# kulgurpowerproto.net
KiCad netlist of a schematic drawn in EAGLE
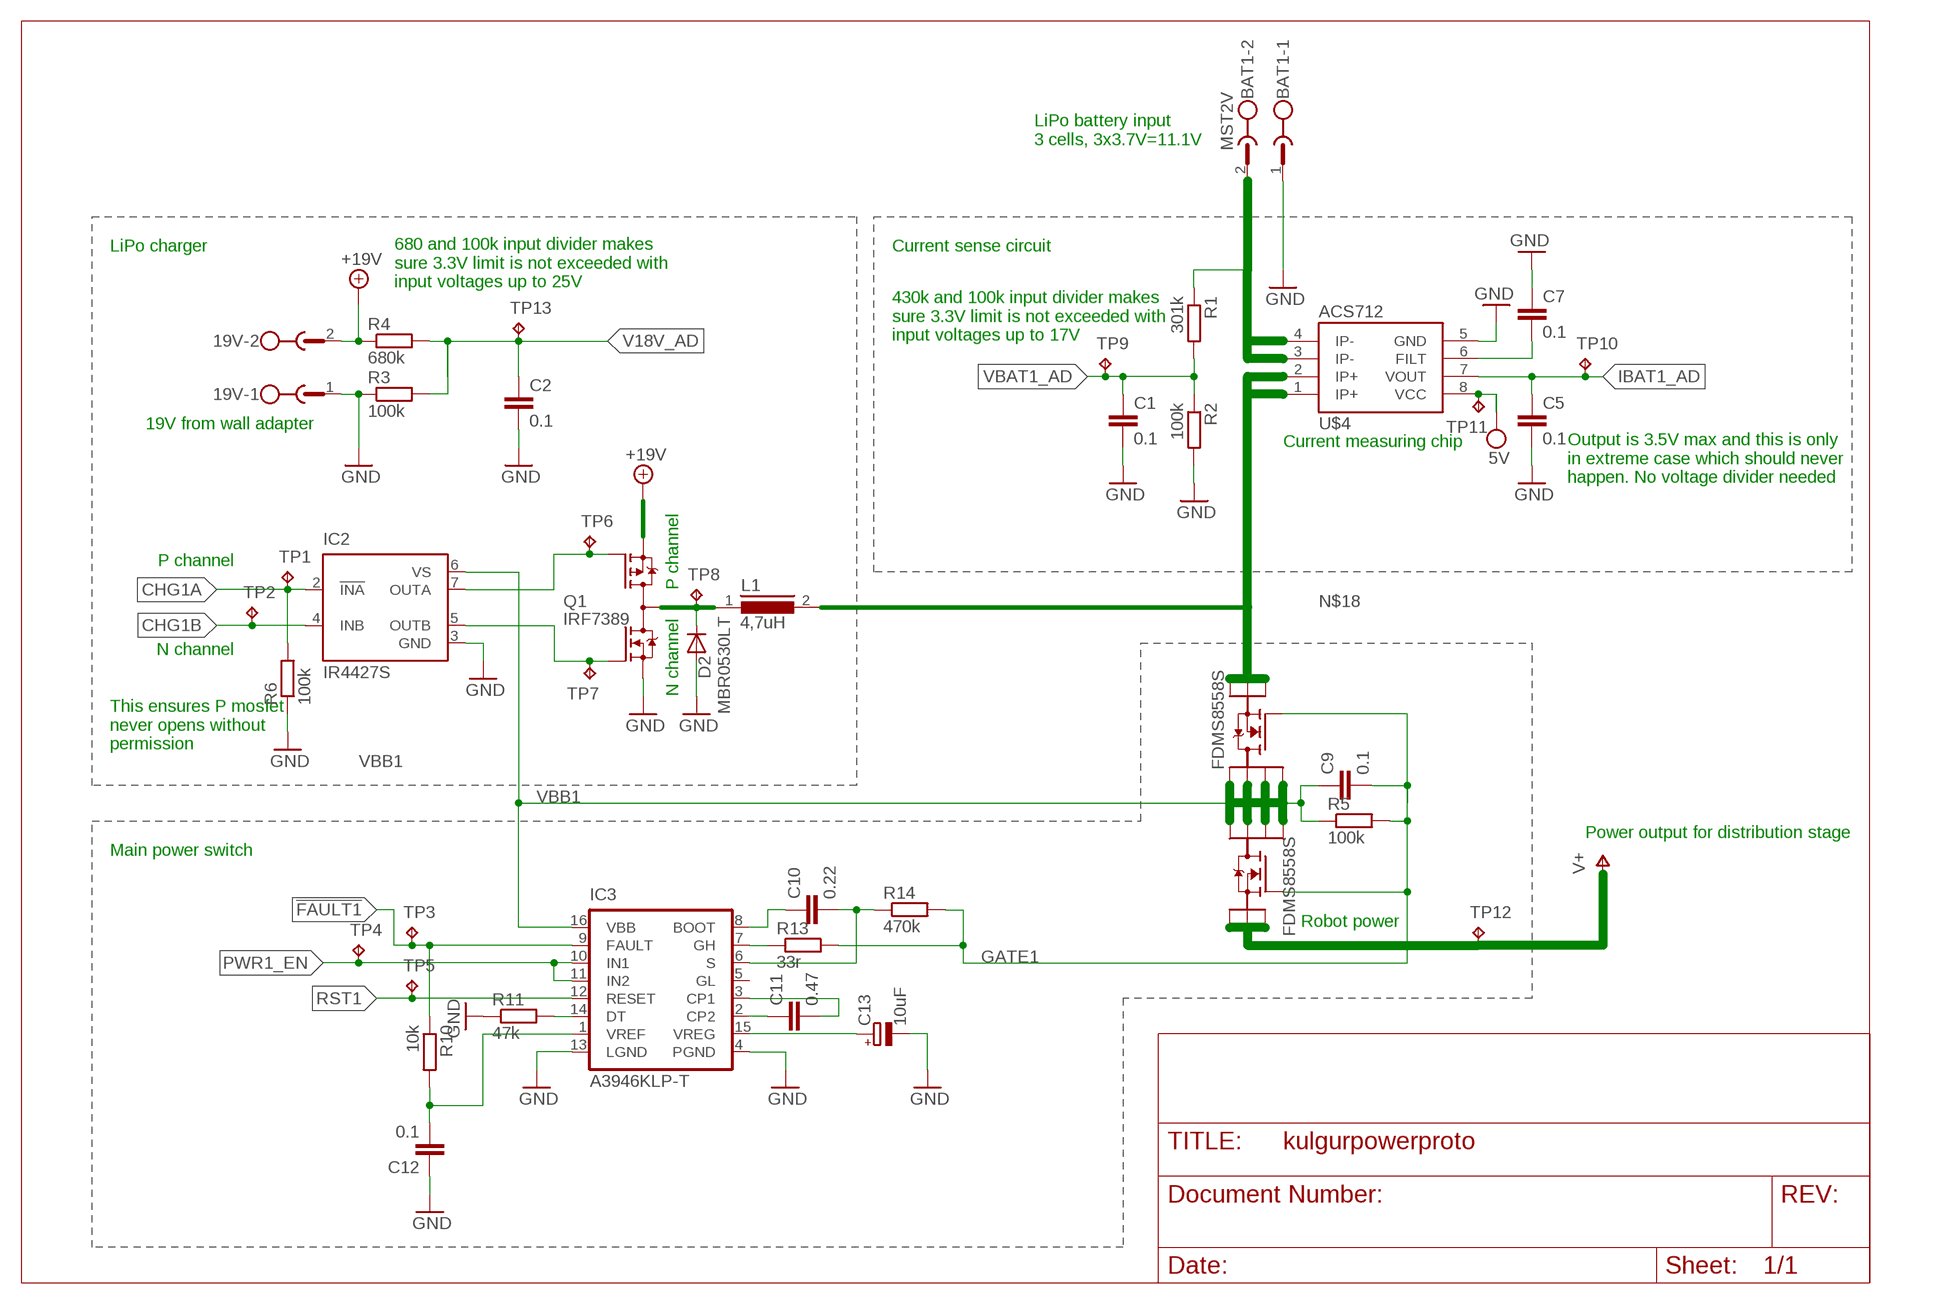
[diagram p0: schematic, sheet 1]

(export (version "E")
  (design (tool "Eeschema 10.0.6"))
  (components
    (comp (ref "19V")
      (value "MST2V")
      (footprint "eagle-import:MSTBV2")
      (fields (field (name "OC_FARNELL") "unknown") (field (name "OC_NEWARK") "unknown"))
      (libsource (lib "eagle-import") (part "MST2V"))
    )
    (comp (ref "BAT1")
      (value "MST2V")
      (footprint "eagle-import:MSTBV2")
      (fields (field (name "OC_FARNELL") "unknown") (field (name "OC_NEWARK") "unknown"))
      (libsource (lib "eagle-import") (part "MST2V"))
    )
    (comp (ref "C1")
      (value "0.1")
      (footprint "eagle-import:C0603")
      (libsource (lib "eagle-import") (part "C-EUC0603"))
    )
    (comp (ref "C2")
      (value "0.1")
      (footprint "eagle-import:C0603")
      (libsource (lib "eagle-import") (part "C-EUC0603"))
    )
    (comp (ref "C5")
      (value "0.1")
      (footprint "eagle-import:C0603")
      (libsource (lib "eagle-import") (part "C-EUC0603"))
    )
    (comp (ref "C7")
      (value "0.1")
      (footprint "eagle-import:C0603")
      (libsource (lib "eagle-import") (part "C-EUC0603"))
    )
    (comp (ref "C9")
      (value "0.1")
      (footprint "eagle-import:C0603")
      (libsource (lib "eagle-import") (part "resistor_C-EUC0603"))
    )
    (comp (ref "C10")
      (value "0.22")
      (footprint "eagle-import:C0603")
      (libsource (lib "eagle-import") (part "resistor_C-EUC0603"))
    )
    (comp (ref "C11")
      (value "0.47")
      (footprint "eagle-import:C0603")
      (libsource (lib "eagle-import") (part "resistor_C-EUC0603"))
    )
    (comp (ref "C12")
      (value "0.1")
      (footprint "eagle-import:C0603")
      (libsource (lib "eagle-import") (part "resistor_C-EUC0603"))
    )
    (comp (ref "C13")
      (value "10uF")
      (footprint "eagle-import:A_3216-18R")
      (libsource (lib "eagle-import") (part "CPOL-EUA/3216-18R"))
    )
    (comp (ref "D2")
      (value "MBR0530LT")
      (footprint "eagle-import:SOD123")
      (libsource (lib "eagle-import") (part "MBR0520LT"))
    )
    (comp (ref "IC2")
      (value "IR4427S")
      (footprint "eagle-import:SO08")
      (fields (field (name "MF") "INTERNATIONAL RECTIFIER(IR)") (field (name "MPN") "IR4428STR"))
      (libsource (lib "eagle-import") (part "IR4428S"))
    )
    (comp (ref "IC3")
      (value "A3946KLP-T")
      (footprint "eagle-import:TSSOP16E")
      (libsource (lib "eagle-import") (part "A3946KLP-T"))
    )
    (comp (ref "L1")
      (value "4,7uH")
      (footprint "eagle-import:DR73")
      (libsource (lib "eagle-import") (part "DR73"))
    )
    (comp (ref "Q1")
      (value "IRF7389")
      (footprint "eagle-import:SO08-IRF")
      (libsource (lib "eagle-import") (part "IRF7389"))
    )
    (comp (ref "R1")
      (value "301k")
      (footprint "eagle-import:R0603")
      (libsource (lib "eagle-import") (part "R-EU_R0603"))
    )
    (comp (ref "R2")
      (value "100k")
      (footprint "eagle-import:R0603")
      (libsource (lib "eagle-import") (part "R-EU_R0603"))
    )
    (comp (ref "R3")
      (value "100k")
      (footprint "eagle-import:R0603")
      (libsource (lib "eagle-import") (part "R-EU_R0603"))
    )
    (comp (ref "R4")
      (value "680k")
      (footprint "eagle-import:R0603")
      (libsource (lib "eagle-import") (part "R-EU_R0603"))
    )
    (comp (ref "R5")
      (value "100k")
      (footprint "eagle-import:R0603")
      (libsource (lib "eagle-import") (part "R-EU_R0603"))
    )
    (comp (ref "R6")
      (value "100k")
      (footprint "eagle-import:R0603")
      (libsource (lib "eagle-import") (part "R-EU_R0603"))
    )
    (comp (ref "R10")
      (value "10k")
      (footprint "eagle-import:R0603")
      (libsource (lib "eagle-import") (part "R-EU_R0603"))
    )
    (comp (ref "R11")
      (value "47k")
      (footprint "eagle-import:R0603")
      (libsource (lib "eagle-import") (part "R-EU_R0603"))
    )
    (comp (ref "R13")
      (value "33r")
      (footprint "eagle-import:R0603")
      (libsource (lib "eagle-import") (part "R-EU_R0603"))
    )
    (comp (ref "R14")
      (value "470k")
      (footprint "eagle-import:R0603")
      (libsource (lib "eagle-import") (part "R-EU_R0603"))
    )
    (comp (ref "TP1")
      (value "TPB2,54")
      (footprint "eagle-import:B2,54")
      (libsource (lib "eagle-import") (part "TPB2,54"))
    )
    (comp (ref "TP2")
      (value "TPB2,54")
      (footprint "eagle-import:B2,54")
      (libsource (lib "eagle-import") (part "TPB2,54"))
    )
    (comp (ref "TP3")
      (value "TPB2,54")
      (footprint "eagle-import:B2,54")
      (libsource (lib "eagle-import") (part "TPB2,54"))
    )
    (comp (ref "TP4")
      (value "TPB2,54")
      (footprint "eagle-import:B2,54")
      (libsource (lib "eagle-import") (part "TPB2,54"))
    )
    (comp (ref "TP5")
      (value "TPB2,54")
      (footprint "eagle-import:B2,54")
      (libsource (lib "eagle-import") (part "TPB2,54"))
    )
    (comp (ref "TP6")
      (value "TPB2,54")
      (footprint "eagle-import:B2,54")
      (libsource (lib "eagle-import") (part "TPB2,54"))
    )
    (comp (ref "TP7")
      (value "TPB2,54")
      (footprint "eagle-import:B2,54")
      (libsource (lib "eagle-import") (part "TPB2,54"))
    )
    (comp (ref "TP8")
      (value "TPB2,54")
      (footprint "eagle-import:B2,54")
      (libsource (lib "eagle-import") (part "TPB2,54"))
    )
    (comp (ref "TP9")
      (value "TPB2,54")
      (footprint "eagle-import:B2,54")
      (libsource (lib "eagle-import") (part "TPB2,54"))
    )
    (comp (ref "TP10")
      (value "TPB2,54")
      (footprint "eagle-import:B2,54")
      (libsource (lib "eagle-import") (part "TPB2,54"))
    )
    (comp (ref "TP11")
      (value "TPB2,54")
      (footprint "eagle-import:B2,54")
      (libsource (lib "eagle-import") (part "TPB2,54"))
    )
    (comp (ref "TP12")
      (value "TPB2,54")
      (footprint "eagle-import:B2,54")
      (libsource (lib "eagle-import") (part "TPB2,54"))
    )
    (comp (ref "TP13")
      (value "TPB2,54")
      (footprint "eagle-import:B2,54")
      (libsource (lib "eagle-import") (part "TPB2,54"))
    )
    (comp (ref "U$2")
      (value "FDMS8558S")
      (footprint "eagle-import:POWER56")
      (libsource (lib "eagle-import") (part "FDMS8558S"))
    )
    (comp (ref "U$3")
      (value "FDMS8558S")
      (footprint "eagle-import:POWER56")
      (libsource (lib "eagle-import") (part "FDMS8558S"))
    )
    (comp (ref "U$4")
      (value "ACS712")
      (footprint "eagle-import:SO08")
      (libsource (lib "eagle-import") (part "ACS712"))
    )
  )
  (nets
    (net (code "1") (name "+19V") (class "Default")
      (node (ref "19V") (pin "2") (pinfunction "1_2") (pintype "passive"))
      (node (ref "Q1") (pin "3") (pinfunction "P-S_3") (pintype "passive"))
      (node (ref "R4") (pin "1") (pinfunction "1_1") (pintype "passive"))
    )
    (net (code "2") (name "/GATE1") (class "Default")
      (node (ref "C9") (pin "2") (pinfunction "2_2") (pintype "passive"))
      (node (ref "R13") (pin "2") (pinfunction "2_2") (pintype "passive"))
      (node (ref "R14") (pin "2") (pinfunction "2_2") (pintype "passive"))
      (node (ref "R5") (pin "2") (pinfunction "2_2") (pintype "passive"))
      (node (ref "U$2") (pin "P$4") (pinfunction "G_P$4") (pintype "passive"))
      (node (ref "U$3") (pin "P$4") (pinfunction "G_P$4") (pintype "passive"))
    )
    (net (code "3") (name "/N$18") (class "Default")
      (node (ref "L1") (pin "2") (pinfunction "2_2") (pintype "passive"))
      (node (ref "U$2") (pin "P$1") (pinfunction "S1_P$1") (pintype "passive"))
      (node (ref "U$2") (pin "P$2") (pinfunction "S2_P$2") (pintype "passive"))
      (node (ref "U$2") (pin "P$3") (pinfunction "S3_P$3") (pintype "passive"))
      (node (ref "U$4") (pin "1") (pinfunction "IP+_1") (pintype "bidirectional"))
      (node (ref "U$4") (pin "2") (pinfunction "IP+_2") (pintype "bidirectional"))
    )
    (net (code "4") (name "/VBB1") (class "Default")
      (node (ref "C9") (pin "1") (pinfunction "1_1") (pintype "passive"))
      (node (ref "IC2") (pin "6") (pinfunction "VS_6") (pintype "power_in"))
      (node (ref "IC3") (pin "16") (pinfunction "VBB_16") (pintype "input"))
      (node (ref "R5") (pin "1") (pinfunction "1_1") (pintype "passive"))
      (node (ref "U$2") (pin "P$5") (pinfunction "D4_P$5") (pintype "passive"))
      (node (ref "U$2") (pin "P$6") (pinfunction "D3_P$6") (pintype "passive"))
      (node (ref "U$2") (pin "P$7") (pinfunction "D2_P$7") (pintype "passive"))
      (node (ref "U$2") (pin "P$8") (pinfunction "D1_P$8") (pintype "passive"))
      (node (ref "U$3") (pin "P$5") (pinfunction "D4_P$5") (pintype "passive"))
      (node (ref "U$3") (pin "P$6") (pinfunction "D3_P$6") (pintype "passive"))
      (node (ref "U$3") (pin "P$7") (pinfunction "D2_P$7") (pintype "passive"))
      (node (ref "U$3") (pin "P$8") (pinfunction "D1_P$8") (pintype "passive"))
    )
    (net (code "5") (name "/~{FAULT1}") (class "Default")
      (node (ref "IC3") (pin "9") (pinfunction "FAULT_9") (pintype "output"))
      (node (ref "R10") (pin "1") (pinfunction "1_1") (pintype "passive"))
      (node (ref "TP3") (pin "TP") (pinfunction "TP_TP") (pintype "input"))
    )
    (net (code "6") (name "5V") (class "Default")
      (node (ref "TP11") (pin "TP") (pinfunction "TP_TP") (pintype "input"))
      (node (ref "U$4") (pin "8") (pinfunction "VCC_8") (pintype "bidirectional"))
    )
    (net (code "7") (name "CHG1A") (class "Default")
      (node (ref "IC2") (pin "2") (pinfunction "~{INA}_2") (pintype "input"))
      (node (ref "R6") (pin "2") (pinfunction "2_2") (pintype "passive"))
      (node (ref "TP1") (pin "TP") (pinfunction "TP_TP") (pintype "input"))
    )
    (net (code "8") (name "CHG1B") (class "Default")
      (node (ref "IC2") (pin "4") (pinfunction "INB_4") (pintype "input"))
      (node (ref "TP2") (pin "TP") (pinfunction "TP_TP") (pintype "input"))
    )
    (net (code "9") (name "GND") (class "Default")
      (node (ref "19V") (pin "1") (pinfunction "1_1") (pintype "passive"))
      (node (ref "BAT1") (pin "1") (pinfunction "1_1") (pintype "passive"))
      (node (ref "C1") (pin "2") (pinfunction "2_2") (pintype "passive"))
      (node (ref "C12") (pin "1") (pinfunction "1_1") (pintype "passive"))
      (node (ref "C13") (pin "-") (pinfunction "-_-") (pintype "passive"))
      (node (ref "C2") (pin "2") (pinfunction "2_2") (pintype "passive"))
      (node (ref "C5") (pin "2") (pinfunction "2_2") (pintype "passive"))
      (node (ref "C7") (pin "1") (pinfunction "1_1") (pintype "passive"))
      (node (ref "D2") (pin "A") (pinfunction "A_A") (pintype "passive"))
      (node (ref "IC2") (pin "3") (pinfunction "GND_3") (pintype "power_in"))
      (node (ref "IC3") (pin "13") (pinfunction "LGND_13") (pintype "power_in"))
      (node (ref "IC3") (pin "4") (pinfunction "PGND_4") (pintype "power_in"))
      (node (ref "Q1") (pin "1") (pinfunction "N-S_1") (pintype "passive"))
      (node (ref "R11") (pin "1") (pinfunction "1_1") (pintype "passive"))
      (node (ref "R2") (pin "2") (pinfunction "2_2") (pintype "passive"))
      (node (ref "R3") (pin "1") (pinfunction "1_1") (pintype "passive"))
      (node (ref "R6") (pin "1") (pinfunction "1_1") (pintype "passive"))
      (node (ref "U$4") (pin "5") (pinfunction "GND_5") (pintype "bidirectional"))
    )
    (net (code "10") (name "IBAT1_AD") (class "Default")
      (node (ref "C5") (pin "1") (pinfunction "1_1") (pintype "passive"))
      (node (ref "TP10") (pin "TP") (pinfunction "TP_TP") (pintype "input"))
      (node (ref "U$4") (pin "7") (pinfunction "VOUT_7") (pintype "bidirectional"))
    )
    (net (code "11") (name "Net-(BAT1B-1)") (class "Default")
      (node (ref "BAT1") (pin "2") (pinfunction "1_2") (pintype "passive"))
      (node (ref "R1") (pin "1") (pinfunction "1_1") (pintype "passive"))
      (node (ref "U$4") (pin "3") (pinfunction "IP-_3") (pintype "bidirectional"))
      (node (ref "U$4") (pin "4") (pinfunction "IP-_4") (pintype "bidirectional"))
    )
    (net (code "12") (name "Net-(D2-PadC)") (class "Default")
      (node (ref "D2") (pin "C") (pinfunction "C_C") (pintype "passive"))
      (node (ref "L1") (pin "1") (pinfunction "1_1") (pintype "passive"))
      (node (ref "Q1") (pin "5") (pinfunction "D_5") (pintype "passive"))
      (node (ref "Q1") (pin "6") (pinfunction "D_6") (pintype "passive"))
      (node (ref "Q1") (pin "7") (pinfunction "D_7") (pintype "passive"))
      (node (ref "Q1") (pin "8") (pinfunction "D_8") (pintype "passive"))
      (node (ref "TP8") (pin "TP") (pinfunction "TP_TP") (pintype "input"))
    )
    (net (code "13") (name "Net-(IC2-OUTA)") (class "Default")
      (node (ref "IC2") (pin "7") (pinfunction "OUTA_7") (pintype "output"))
      (node (ref "Q1") (pin "4") (pinfunction "P-G_4") (pintype "passive"))
      (node (ref "TP6") (pin "TP") (pinfunction "TP_TP") (pintype "input"))
    )
    (net (code "14") (name "Net-(IC2-OUTB)") (class "Default")
      (node (ref "IC2") (pin "5") (pinfunction "OUTB_5") (pintype "output"))
      (node (ref "Q1") (pin "2") (pinfunction "N-G_2") (pintype "passive"))
      (node (ref "TP7") (pin "TP") (pinfunction "TP_TP") (pintype "input"))
    )
    (net (code "15") (name "Net-(IC3-BOOT)") (class "Default")
      (node (ref "C10") (pin "1") (pinfunction "1_1") (pintype "passive"))
      (node (ref "IC3") (pin "8") (pinfunction "BOOT_8") (pintype "input"))
    )
    (net (code "16") (name "Net-(IC3-CP1)") (class "Default")
      (node (ref "C11") (pin "2") (pinfunction "2_2") (pintype "passive"))
      (node (ref "IC3") (pin "3") (pinfunction "CP1_3") (pintype "passive"))
    )
    (net (code "17") (name "Net-(IC3-CP2)") (class "Default")
      (node (ref "C11") (pin "1") (pinfunction "1_1") (pintype "passive"))
      (node (ref "IC3") (pin "2") (pinfunction "CP2_2") (pintype "passive"))
    )
    (net (code "18") (name "Net-(IC3-DT)") (class "Default")
      (node (ref "IC3") (pin "14") (pinfunction "DT_14") (pintype "passive"))
      (node (ref "R11") (pin "2") (pinfunction "2_2") (pintype "passive"))
    )
    (net (code "19") (name "Net-(IC3-GH)") (class "Default")
      (node (ref "IC3") (pin "7") (pinfunction "GH_7") (pintype "output"))
      (node (ref "R13") (pin "1") (pinfunction "1_1") (pintype "passive"))
    )
    (net (code "20") (name "Net-(IC3-S)") (class "Default")
      (node (ref "C10") (pin "2") (pinfunction "2_2") (pintype "passive"))
      (node (ref "IC3") (pin "6") (pinfunction "S_6") (pintype "input"))
      (node (ref "R14") (pin "1") (pinfunction "1_1") (pintype "passive"))
    )
    (net (code "21") (name "Net-(IC3-VREF)") (class "Default")
      (node (ref "C12") (pin "2") (pinfunction "2_2") (pintype "passive"))
      (node (ref "IC3") (pin "1") (pinfunction "VREF_1") (pintype "passive"))
      (node (ref "R10") (pin "2") (pinfunction "2_2") (pintype "passive"))
    )
    (net (code "22") (name "Net-(IC3-VREG)") (class "Default")
      (node (ref "C13") (pin "+") (pinfunction "+_+") (pintype "passive"))
      (node (ref "IC3") (pin "15") (pinfunction "VREG_15") (pintype "passive"))
    )
    (net (code "23") (name "Net-(U$4-FILT)") (class "Default")
      (node (ref "C7") (pin "2") (pinfunction "2_2") (pintype "passive"))
      (node (ref "U$4") (pin "6") (pinfunction "FILT_6") (pintype "bidirectional"))
    )
    (net (code "24") (name "PWR1_EN") (class "Default")
      (node (ref "IC3") (pin "10") (pinfunction "IN1_10") (pintype "input"))
      (node (ref "IC3") (pin "11") (pinfunction "IN2_11") (pintype "input"))
      (node (ref "TP4") (pin "TP") (pinfunction "TP_TP") (pintype "input"))
    )
    (net (code "25") (name "RST1") (class "Default")
      (node (ref "IC3") (pin "12") (pinfunction "RESET_12") (pintype "input"))
      (node (ref "TP5") (pin "TP") (pinfunction "TP_TP") (pintype "input"))
    )
    (net (code "26") (name "V+") (class "Default")
      (node (ref "TP12") (pin "TP") (pinfunction "TP_TP") (pintype "input"))
      (node (ref "U$3") (pin "P$1") (pinfunction "S1_P$1") (pintype "passive"))
      (node (ref "U$3") (pin "P$2") (pinfunction "S2_P$2") (pintype "passive"))
      (node (ref "U$3") (pin "P$3") (pinfunction "S3_P$3") (pintype "passive"))
    )
    (net (code "27") (name "V18V_AD") (class "Default")
      (node (ref "C2") (pin "1") (pinfunction "1_1") (pintype "passive"))
      (node (ref "R3") (pin "2") (pinfunction "2_2") (pintype "passive"))
      (node (ref "R4") (pin "2") (pinfunction "2_2") (pintype "passive"))
      (node (ref "TP13") (pin "TP") (pinfunction "TP_TP") (pintype "input"))
    )
    (net (code "28") (name "VBAT1_AD") (class "Default")
      (node (ref "C1") (pin "1") (pinfunction "1_1") (pintype "passive"))
      (node (ref "R1") (pin "2") (pinfunction "2_2") (pintype "passive"))
      (node (ref "R2") (pin "1") (pinfunction "1_1") (pintype "passive"))
      (node (ref "TP9") (pin "TP") (pinfunction "TP_TP") (pintype "input"))
    )
    (net (code "29") (name "unconnected-(IC3-GL-Pad5)") (class "Default")
      (node (ref "IC3") (pin "5") (pinfunction "GL_5") (pintype "output"))
    )
  )
)
